# ESP8266_usb_spi_connector7.net
KiCad netlist of a schematic drawn in EAGLE
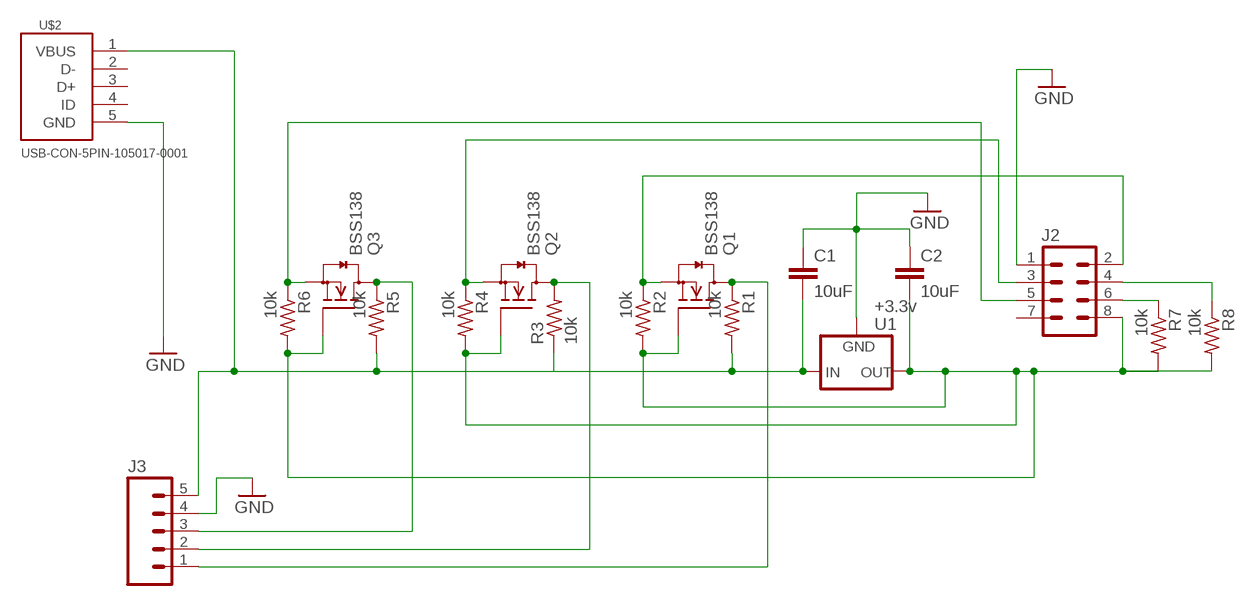
[diagram p0: schematic, sheet 1]

(export (version "E")
  (design (tool "Eeschema 10.0.6"))
  (components
    (comp (ref "C1")
      (value "10uF")
      (footprint "eagle-import:1206")
      (libsource (lib "eagle-import") (part "CAP1206"))
    )
    (comp (ref "C2")
      (value "10uF")
      (footprint "eagle-import:1206")
      (libsource (lib "eagle-import") (part "CAP1206"))
    )
    (comp (ref "J2")
      (value "M04X2")
      (footprint "eagle-import:2X4")
      (libsource (lib "eagle-import") (part "M04X2"))
    )
    (comp (ref "J3")
      (value "M05PTH")
      (footprint "eagle-import:1X05")
      (libsource (lib "eagle-import") (part "M05PTH"))
    )
    (comp (ref "Q1")
      (value "BSS138")
      (footprint "eagle-import:SOT23")
      (libsource (lib "eagle-import") (part "BSS138"))
    )
    (comp (ref "Q2")
      (value "BSS138")
      (footprint "eagle-import:SOT23")
      (libsource (lib "eagle-import") (part "BSS138"))
    )
    (comp (ref "Q3")
      (value "BSS138")
      (footprint "eagle-import:SOT23")
      (libsource (lib "eagle-import") (part "BSS138"))
    )
    (comp (ref "R1")
      (value "10k")
      (footprint "eagle-import:M1206")
      (libsource (lib "eagle-import") (part "R-US_M1206"))
    )
    (comp (ref "R2")
      (value "10k")
      (footprint "eagle-import:M1206")
      (libsource (lib "eagle-import") (part "R-US_M1206"))
    )
    (comp (ref "R3")
      (value "10k")
      (footprint "eagle-import:M1206")
      (libsource (lib "eagle-import") (part "R-US_M1206"))
    )
    (comp (ref "R4")
      (value "10k")
      (footprint "eagle-import:M1206")
      (libsource (lib "eagle-import") (part "R-US_M1206"))
    )
    (comp (ref "R5")
      (value "10k")
      (footprint "eagle-import:M1206")
      (libsource (lib "eagle-import") (part "R-US_M1206"))
    )
    (comp (ref "R6")
      (value "10k")
      (footprint "eagle-import:M1206")
      (libsource (lib "eagle-import") (part "R-US_M1206"))
    )
    (comp (ref "R7")
      (value "10k")
      (footprint "eagle-import:M1206")
      (libsource (lib "eagle-import") (part "R-US_M1206"))
    )
    (comp (ref "R8")
      (value "10k")
      (footprint "eagle-import:M1206")
      (libsource (lib "eagle-import") (part "R-US_M1206"))
    )
    (comp (ref "U$2")
      (value "USB-CON-5PIN-105017-0001")
      (footprint "eagle-import:USB-MICRO-MOLEX-105017-0001")
      (libsource (lib "eagle-import") (part "USB-CON-5PIN-105017-0001"))
    )
    (comp (ref "U1")
      (value "+3.3v")
      (footprint "eagle-import:TO-252")
      (libsource (lib "eagle-import") (part "V_REG_78XX7812"))
    )
  )
  (nets
    (net (code "1") (name "GND") (class "Default")
      (node (ref "C1") (pin "1") (pinfunction "1_1") (pintype "passive"))
      (node (ref "C2") (pin "1") (pinfunction "1_1") (pintype "passive"))
      (node (ref "J2") (pin "1") (pinfunction "1_1") (pintype "passive"))
      (node (ref "J3") (pin "4") (pinfunction "4_4") (pintype "passive"))
      (node (ref "U$2") (pin "5") (pinfunction "GND_5") (pintype "power_in"))
      (node (ref "U1") (pin "3") (pinfunction "GND_3") (pintype "input"))
    )
    (net (code "2") (name "Net-(J2-Pad4)") (class "Default")
      (node (ref "J2") (pin "4") (pinfunction "4_4") (pintype "passive"))
      (node (ref "R8") (pin "1") (pinfunction "1_1") (pintype "passive"))
    )
    (net (code "3") (name "Net-(J2-Pad6)") (class "Default")
      (node (ref "J2") (pin "6") (pinfunction "6_6") (pintype "passive"))
      (node (ref "R7") (pin "1") (pinfunction "1_1") (pintype "passive"))
    )
    (net (code "4") (name "Net-(Q1-D)") (class "Default")
      (node (ref "J3") (pin "1") (pinfunction "1_1") (pintype "passive"))
      (node (ref "Q1") (pin "3") (pinfunction "D_3") (pintype "passive"))
      (node (ref "R1") (pin "1") (pinfunction "1_1") (pintype "passive"))
    )
    (net (code "5") (name "Net-(Q1-G)") (class "Default")
      (node (ref "C2") (pin "2") (pinfunction "2_2") (pintype "passive"))
      (node (ref "J2") (pin "8") (pinfunction "8_8") (pintype "passive"))
      (node (ref "Q1") (pin "1") (pinfunction "G_1") (pintype "passive"))
      (node (ref "Q2") (pin "1") (pinfunction "G_1") (pintype "passive"))
      (node (ref "Q3") (pin "1") (pinfunction "G_1") (pintype "passive"))
      (node (ref "R2") (pin "2") (pinfunction "2_2") (pintype "passive"))
      (node (ref "R4") (pin "2") (pinfunction "2_2") (pintype "passive"))
      (node (ref "R6") (pin "2") (pinfunction "2_2") (pintype "passive"))
      (node (ref "R7") (pin "2") (pinfunction "2_2") (pintype "passive"))
      (node (ref "R8") (pin "2") (pinfunction "2_2") (pintype "passive"))
      (node (ref "U1") (pin "2") (pinfunction "OUT_2") (pintype "passive"))
    )
    (net (code "6") (name "Net-(Q1-S)") (class "Default")
      (node (ref "J2") (pin "2") (pinfunction "2_2") (pintype "passive"))
      (node (ref "Q1") (pin "2") (pinfunction "S_2") (pintype "passive"))
      (node (ref "R2") (pin "1") (pinfunction "1_1") (pintype "passive"))
    )
    (net (code "7") (name "Net-(Q2-D)") (class "Default")
      (node (ref "J3") (pin "2") (pinfunction "2_2") (pintype "passive"))
      (node (ref "Q2") (pin "3") (pinfunction "D_3") (pintype "passive"))
      (node (ref "R3") (pin "2") (pinfunction "2_2") (pintype "passive"))
    )
    (net (code "8") (name "Net-(Q2-S)") (class "Default")
      (node (ref "J2") (pin "3") (pinfunction "3_3") (pintype "passive"))
      (node (ref "Q2") (pin "2") (pinfunction "S_2") (pintype "passive"))
      (node (ref "R4") (pin "1") (pinfunction "1_1") (pintype "passive"))
    )
    (net (code "9") (name "Net-(Q3-D)") (class "Default")
      (node (ref "J3") (pin "3") (pinfunction "3_3") (pintype "passive"))
      (node (ref "Q3") (pin "3") (pinfunction "D_3") (pintype "passive"))
      (node (ref "R5") (pin "1") (pinfunction "1_1") (pintype "passive"))
    )
    (net (code "10") (name "Net-(Q3-S)") (class "Default")
      (node (ref "J2") (pin "5") (pinfunction "5_5") (pintype "passive"))
      (node (ref "Q3") (pin "2") (pinfunction "S_2") (pintype "passive"))
      (node (ref "R6") (pin "1") (pinfunction "1_1") (pintype "passive"))
    )
    (net (code "11") (name "Net-(U$2-VBUS)") (class "Default")
      (node (ref "C1") (pin "2") (pinfunction "2_2") (pintype "passive"))
      (node (ref "J3") (pin "5") (pinfunction "5_5") (pintype "passive"))
      (node (ref "R1") (pin "2") (pinfunction "2_2") (pintype "passive"))
      (node (ref "R3") (pin "1") (pinfunction "1_1") (pintype "passive"))
      (node (ref "R5") (pin "2") (pinfunction "2_2") (pintype "passive"))
      (node (ref "U$2") (pin "1") (pinfunction "VBUS_1") (pintype "power_in"))
      (node (ref "U1") (pin "1") (pinfunction "IN_1") (pintype "input"))
    )
    (net (code "12") (name "unconnected-(J2-Pad7)") (class "Default")
      (node (ref "J2") (pin "7") (pinfunction "7_7") (pintype "passive"))
    )
    (net (code "13") (name "unconnected-(U$2-D+-Pad3)") (class "Default")
      (node (ref "U$2") (pin "3") (pinfunction "D+_3") (pintype "bidirectional"))
    )
    (net (code "14") (name "unconnected-(U$2-D--Pad2)") (class "Default")
      (node (ref "U$2") (pin "2") (pinfunction "D-_2") (pintype "bidirectional"))
    )
    (net (code "15") (name "unconnected-(U$2-ID-Pad4)") (class "Default")
      (node (ref "U$2") (pin "4") (pinfunction "ID_4") (pintype "bidirectional"))
    )
  )
)
